# BSPD_4.net
KiCad netlist of a schematic drawn in EAGLE
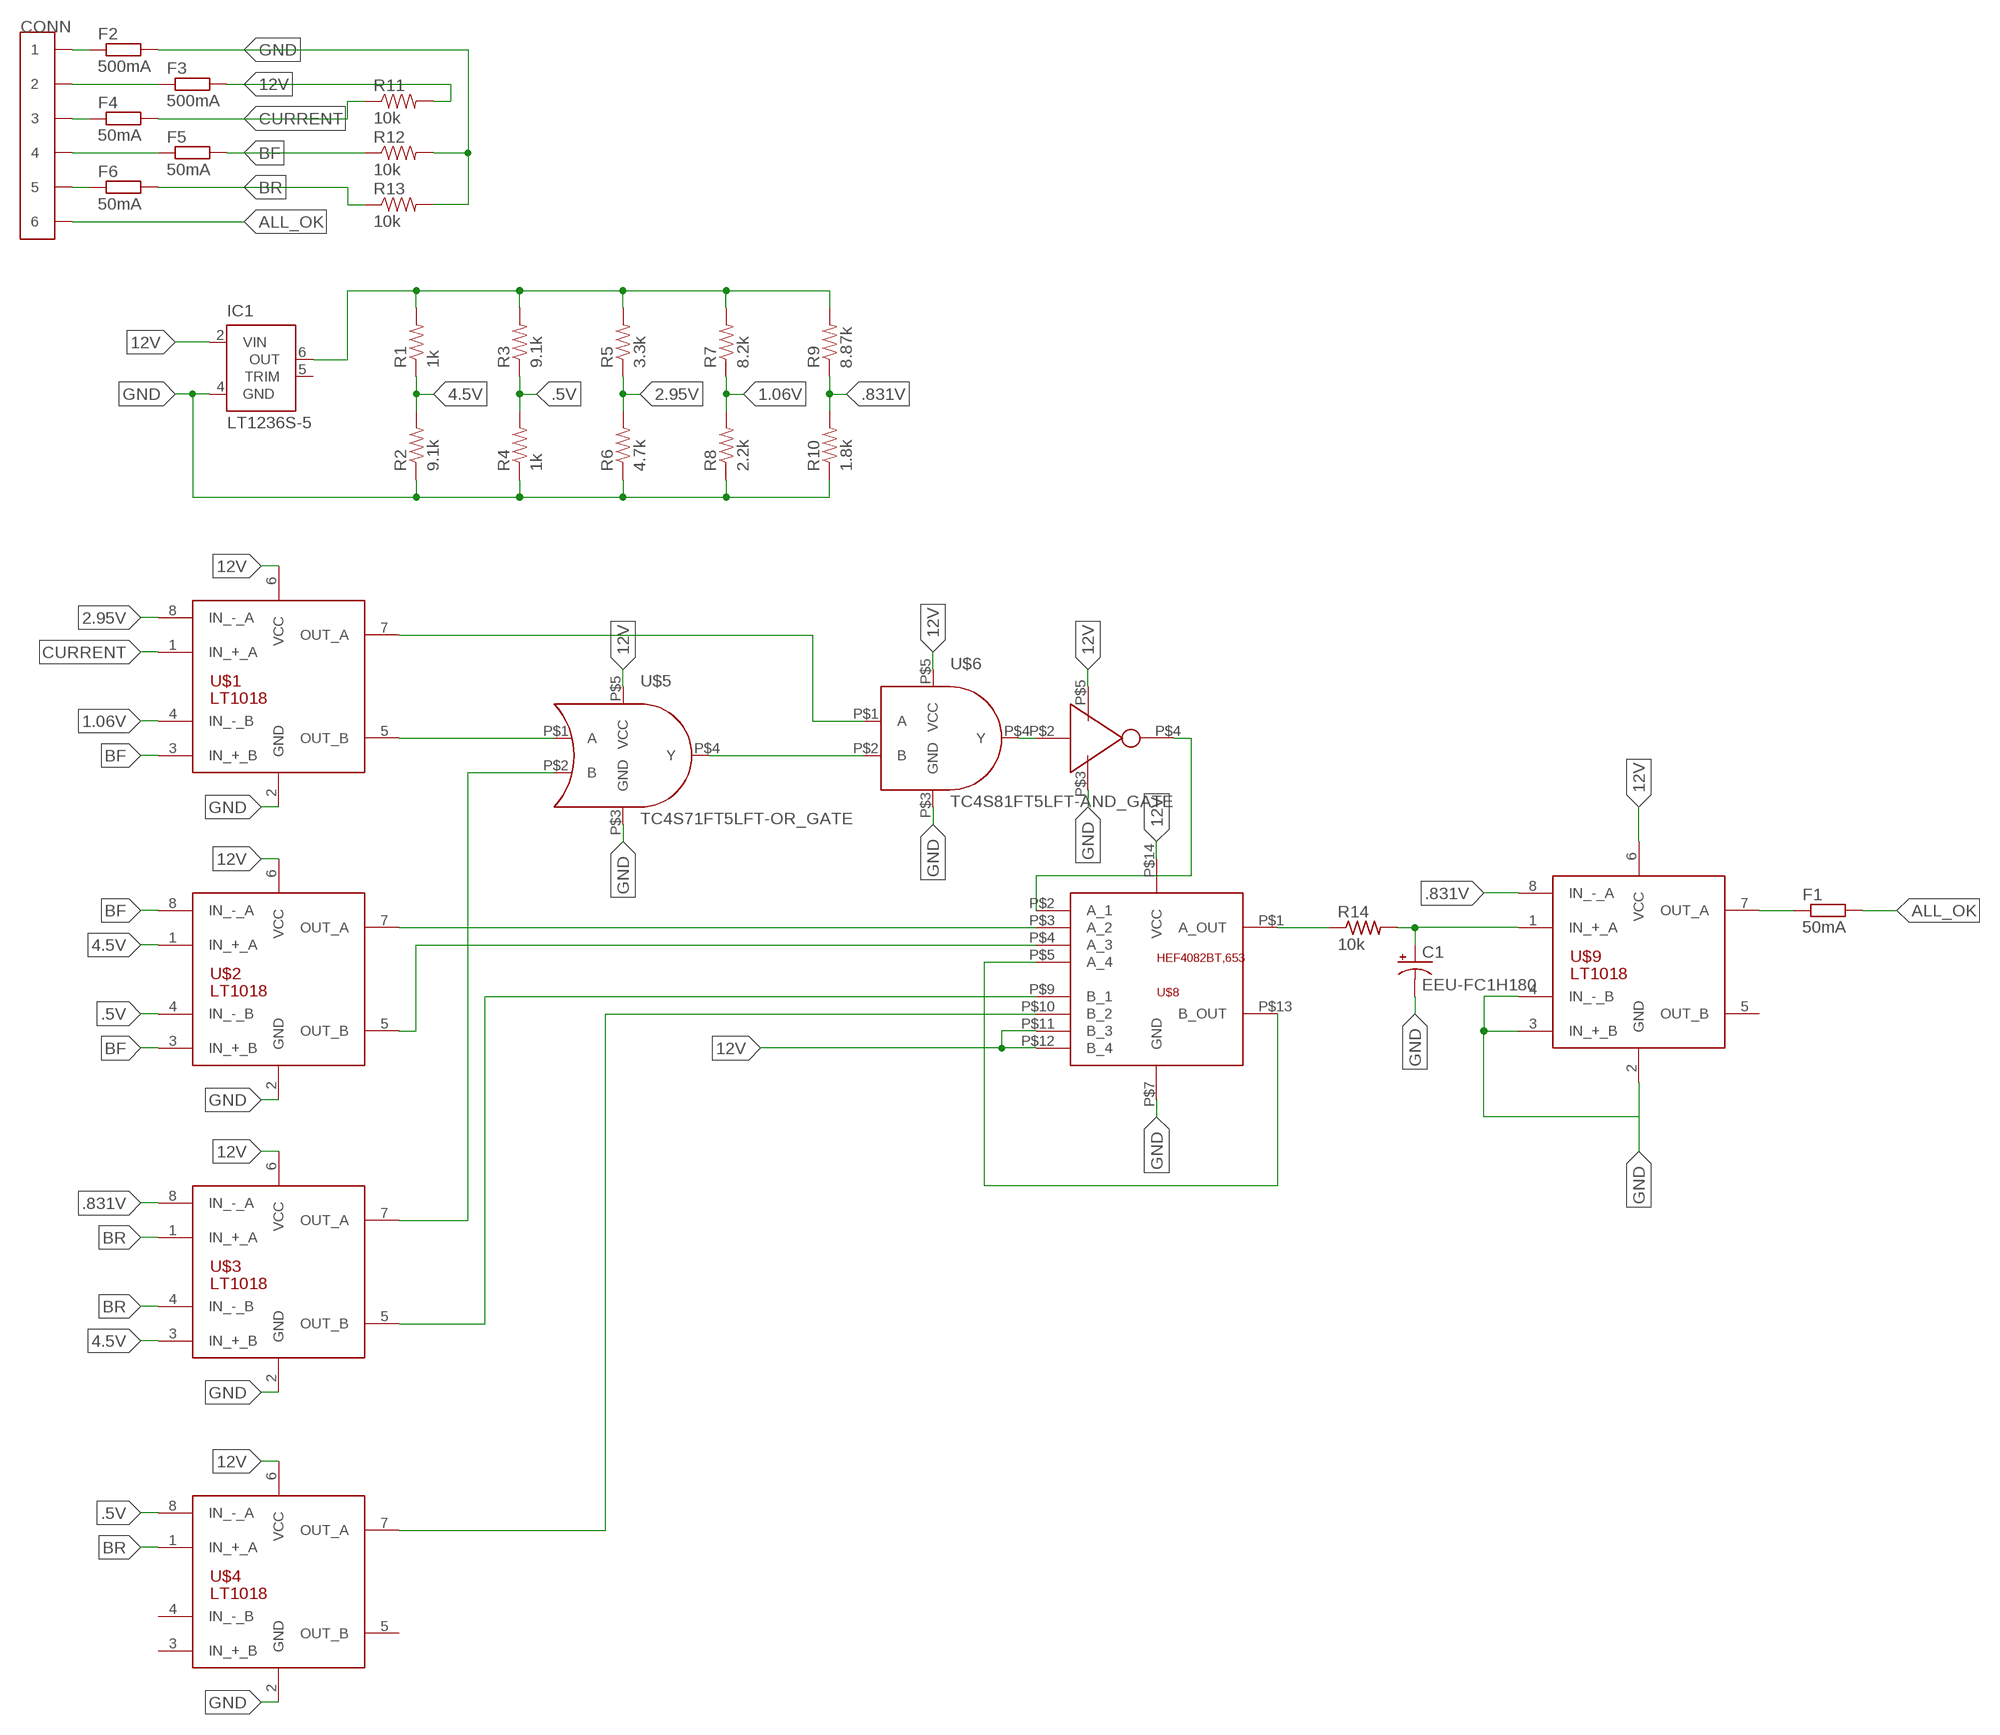
[diagram p0: schematic, sheet 1]

(export (version "E")
  (design (tool "Eeschema 10.0.6"))
  (components
    (comp (ref "C1")
      (value "EEU-FC1H180")
      (footprint "eagle-import:E2-5")
      (libsource (lib "eagle-import") (part "CPOL-USE2-5"))
    )
    (comp (ref "CONN")
      (value "CONN_6")
      (footprint "eagle-import:CONNECTOR_6")
      (libsource (lib "eagle-import") (part "CONN_6"))
    )
    (comp (ref "F1")
      (value "50mA")
      (footprint "eagle-import:R0603")
      (libsource (lib "eagle-import") (part "R-EU_R0603"))
    )
    (comp (ref "F2")
      (value "500mA")
      (footprint "eagle-import:R0603")
      (libsource (lib "eagle-import") (part "R-EU_R0603"))
    )
    (comp (ref "F3")
      (value "500mA")
      (footprint "eagle-import:R0603")
      (libsource (lib "eagle-import") (part "R-EU_R0603"))
    )
    (comp (ref "F4")
      (value "50mA")
      (footprint "eagle-import:R0603")
      (libsource (lib "eagle-import") (part "R-EU_R0603"))
    )
    (comp (ref "F5")
      (value "50mA")
      (footprint "eagle-import:R0603")
      (libsource (lib "eagle-import") (part "R-EU_R0603"))
    )
    (comp (ref "F6")
      (value "50mA")
      (footprint "eagle-import:R0603")
      (libsource (lib "eagle-import") (part "R-EU_R0603"))
    )
    (comp (ref "IC1")
      (value "LT1236S-5")
      (footprint "eagle-import:SOIC8")
      (libsource (lib "eagle-import") (part "LT1236?S-5"))
    )
    (comp (ref "R1")
      (value "1k")
      (footprint "eagle-import:0603-RES")
      (libsource (lib "eagle-import") (part "RESISTOR0603"))
    )
    (comp (ref "R2")
      (value "9.1k")
      (footprint "eagle-import:0603-RES")
      (libsource (lib "eagle-import") (part "RESISTOR0603"))
    )
    (comp (ref "R3")
      (value "9.1k")
      (footprint "eagle-import:0603-RES")
      (libsource (lib "eagle-import") (part "RESISTOR0603"))
    )
    (comp (ref "R4")
      (value "1k")
      (footprint "eagle-import:0603-RES")
      (libsource (lib "eagle-import") (part "RESISTOR0603"))
    )
    (comp (ref "R5")
      (value "3.3k")
      (footprint "eagle-import:0603-RES")
      (libsource (lib "eagle-import") (part "RESISTOR0603"))
    )
    (comp (ref "R6")
      (value "4.7k")
      (footprint "eagle-import:0603-RES")
      (libsource (lib "eagle-import") (part "RESISTOR0603"))
    )
    (comp (ref "R7")
      (value "8.2k")
      (footprint "eagle-import:0603-RES")
      (libsource (lib "eagle-import") (part "RESISTOR0603"))
    )
    (comp (ref "R8")
      (value "2.2k")
      (footprint "eagle-import:0603-RES")
      (libsource (lib "eagle-import") (part "RESISTOR0603"))
    )
    (comp (ref "R9")
      (value "8.87k")
      (footprint "eagle-import:0603-RES")
      (libsource (lib "eagle-import") (part "RESISTOR0603"))
    )
    (comp (ref "R10")
      (value "1.8k")
      (footprint "eagle-import:0603-RES")
      (libsource (lib "eagle-import") (part "RESISTOR0603"))
    )
    (comp (ref "R11")
      (value "10k")
      (footprint "eagle-import:0603-RES")
      (libsource (lib "eagle-import") (part "RESISTOR0603"))
    )
    (comp (ref "R12")
      (value "10k")
      (footprint "eagle-import:0603-RES")
      (libsource (lib "eagle-import") (part "RESISTOR0603"))
    )
    (comp (ref "R13")
      (value "10k")
      (footprint "eagle-import:0603-RES")
      (libsource (lib "eagle-import") (part "RESISTOR0603"))
    )
    (comp (ref "R14")
      (value "10k")
      (footprint "eagle-import:R0603")
      (libsource (lib "eagle-import") (part "R-US_R0603"))
    )
    (comp (ref "U$1")
      (value "LT1018")
      (footprint "eagle-import:SOIC8")
      (libsource (lib "eagle-import") (part "LT1018"))
    )
    (comp (ref "U$2")
      (value "LT1018")
      (footprint "eagle-import:SOIC8")
      (libsource (lib "eagle-import") (part "LT1018"))
    )
    (comp (ref "U$3")
      (value "LT1018")
      (footprint "eagle-import:SOIC8")
      (libsource (lib "eagle-import") (part "LT1018"))
    )
    (comp (ref "U$4")
      (value "LT1018")
      (footprint "eagle-import:SOIC8")
      (libsource (lib "eagle-import") (part "LT1018"))
    )
    (comp (ref "U$5")
      (value "TC4S71FT5LFT-OR_GATE")
      (footprint "eagle-import:SSOP5-P-0.95")
      (libsource (lib "eagle-import") (part "TC4S71FT5LFT-OR_GATE"))
    )
    (comp (ref "U$6")
      (value "TC4S81FT5LFT-AND_GATE")
      (footprint "eagle-import:SSOP5-P-0.95")
      (libsource (lib "eagle-import") (part "TC4S81FT5LFT-AND_GATE"))
    )
    (comp (ref "U$7")
      (value "TC4S69F(TE85L,F)")
      (footprint "eagle-import:SSOP5-P-0.95")
      (libsource (lib "eagle-import") (part "TC4S69F(TE85L,F)"))
    )
    (comp (ref "U$8")
      (value "HEF4082BT,653")
      (footprint "eagle-import:NXP_14_SOIC")
      (libsource (lib "eagle-import") (part "HEF4082BT,653"))
    )
    (comp (ref "U$9")
      (value "LT1018")
      (footprint "eagle-import:SOIC8")
      (libsource (lib "eagle-import") (part "LT1018"))
    )
  )
  (nets
    (net (code "1") (name ".5V") (class "Default")
      (node (ref "R3") (pin "1") (pinfunction "1_1") (pintype "passive"))
      (node (ref "R4") (pin "2") (pinfunction "2_2") (pintype "passive"))
      (node (ref "U$2") (pin "4") (pinfunction "IN_-_B_4") (pintype "input"))
      (node (ref "U$4") (pin "8") (pinfunction "IN_-_A_8") (pintype "input"))
    )
    (net (code "2") (name ".831V") (class "Default")
      (node (ref "R10") (pin "2") (pinfunction "2_2") (pintype "passive"))
      (node (ref "R9") (pin "1") (pinfunction "1_1") (pintype "passive"))
      (node (ref "U$3") (pin "8") (pinfunction "IN_-_A_8") (pintype "input"))
      (node (ref "U$9") (pin "8") (pinfunction "IN_-_A_8") (pintype "input"))
    )
    (net (code "3") (name "1.06V") (class "Default")
      (node (ref "R7") (pin "1") (pinfunction "1_1") (pintype "passive"))
      (node (ref "R8") (pin "2") (pinfunction "2_2") (pintype "passive"))
      (node (ref "U$1") (pin "4") (pinfunction "IN_-_B_4") (pintype "input"))
    )
    (net (code "4") (name "2.95V") (class "Default")
      (node (ref "R5") (pin "1") (pinfunction "1_1") (pintype "passive"))
      (node (ref "R6") (pin "2") (pinfunction "2_2") (pintype "passive"))
      (node (ref "U$1") (pin "8") (pinfunction "IN_-_A_8") (pintype "input"))
    )
    (net (code "5") (name "4.5V") (class "Default")
      (node (ref "R1") (pin "1") (pinfunction "1_1") (pintype "passive"))
      (node (ref "R2") (pin "2") (pinfunction "2_2") (pintype "passive"))
      (node (ref "U$2") (pin "1") (pinfunction "IN_+_A_1") (pintype "input"))
      (node (ref "U$3") (pin "3") (pinfunction "IN_+_B_3") (pintype "input"))
    )
    (net (code "6") (name "12V") (class "Default")
      (node (ref "F3") (pin "2") (pinfunction "2_2") (pintype "passive"))
      (node (ref "IC1") (pin "2") (pinfunction "VIN_2") (pintype "input"))
      (node (ref "R11") (pin "2") (pinfunction "2_2") (pintype "passive"))
      (node (ref "U$1") (pin "6") (pinfunction "VCC_6") (pintype "power_in"))
      (node (ref "U$2") (pin "6") (pinfunction "VCC_6") (pintype "power_in"))
      (node (ref "U$3") (pin "6") (pinfunction "VCC_6") (pintype "power_in"))
      (node (ref "U$4") (pin "6") (pinfunction "VCC_6") (pintype "power_in"))
      (node (ref "U$5") (pin "P$5") (pinfunction "VCC_P$5") (pintype "bidirectional"))
      (node (ref "U$6") (pin "P$5") (pinfunction "VCC_P$5") (pintype "bidirectional"))
      (node (ref "U$7") (pin "P$5") (pinfunction "VCC_P$5") (pintype "power_in"))
      (node (ref "U$8") (pin "P$11") (pinfunction "B_3_P$11") (pintype "open_collector"))
      (node (ref "U$8") (pin "P$12") (pinfunction "B_4_P$12") (pintype "open_collector"))
      (node (ref "U$8") (pin "P$14") (pinfunction "VCC_P$14") (pintype "power_in"))
      (node (ref "U$9") (pin "6") (pinfunction "VCC_6") (pintype "power_in"))
    )
    (net (code "7") (name "ALL_OK") (class "Default")
      (node (ref "CONN") (pin "11") (pinfunction "6_11") (pintype "bidirectional"))
      (node (ref "CONN") (pin "12") (pinfunction "6_12") (pintype "bidirectional"))
      (node (ref "F1") (pin "2") (pinfunction "2_2") (pintype "passive"))
    )
    (net (code "8") (name "BF") (class "Default")
      (node (ref "F5") (pin "2") (pinfunction "2_2") (pintype "passive"))
      (node (ref "R12") (pin "1") (pinfunction "1_1") (pintype "passive"))
      (node (ref "U$1") (pin "3") (pinfunction "IN_+_B_3") (pintype "input"))
      (node (ref "U$2") (pin "3") (pinfunction "IN_+_B_3") (pintype "input"))
      (node (ref "U$2") (pin "8") (pinfunction "IN_-_A_8") (pintype "input"))
    )
    (net (code "9") (name "BR") (class "Default")
      (node (ref "F6") (pin "2") (pinfunction "2_2") (pintype "passive"))
      (node (ref "R13") (pin "1") (pinfunction "1_1") (pintype "passive"))
      (node (ref "U$3") (pin "1") (pinfunction "IN_+_A_1") (pintype "input"))
      (node (ref "U$3") (pin "4") (pinfunction "IN_-_B_4") (pintype "input"))
      (node (ref "U$4") (pin "1") (pinfunction "IN_+_A_1") (pintype "input"))
    )
    (net (code "10") (name "CURRENT") (class "Default")
      (node (ref "F4") (pin "2") (pinfunction "2_2") (pintype "passive"))
      (node (ref "R11") (pin "1") (pinfunction "1_1") (pintype "passive"))
      (node (ref "U$1") (pin "1") (pinfunction "IN_+_A_1") (pintype "input"))
    )
    (net (code "11") (name "GND") (class "Default")
      (node (ref "C1") (pin "-") (pinfunction "-_-") (pintype "passive"))
      (node (ref "F2") (pin "2") (pinfunction "2_2") (pintype "passive"))
      (node (ref "IC1") (pin "4") (pinfunction "GND_4") (pintype "power_in"))
      (node (ref "R10") (pin "1") (pinfunction "1_1") (pintype "passive"))
      (node (ref "R12") (pin "2") (pinfunction "2_2") (pintype "passive"))
      (node (ref "R13") (pin "2") (pinfunction "2_2") (pintype "passive"))
      (node (ref "R2") (pin "1") (pinfunction "1_1") (pintype "passive"))
      (node (ref "R4") (pin "1") (pinfunction "1_1") (pintype "passive"))
      (node (ref "R6") (pin "1") (pinfunction "1_1") (pintype "passive"))
      (node (ref "R8") (pin "1") (pinfunction "1_1") (pintype "passive"))
      (node (ref "U$1") (pin "2") (pinfunction "GND_2") (pintype "power_in"))
      (node (ref "U$2") (pin "2") (pinfunction "GND_2") (pintype "power_in"))
      (node (ref "U$3") (pin "2") (pinfunction "GND_2") (pintype "power_in"))
      (node (ref "U$4") (pin "2") (pinfunction "GND_2") (pintype "power_in"))
      (node (ref "U$5") (pin "P$3") (pinfunction "GND_P$3") (pintype "bidirectional"))
      (node (ref "U$6") (pin "P$3") (pinfunction "GND_P$3") (pintype "bidirectional"))
      (node (ref "U$7") (pin "P$3") (pinfunction "GND_P$3") (pintype "power_in"))
      (node (ref "U$8") (pin "P$7") (pinfunction "GND_P$7") (pintype "power_in"))
      (node (ref "U$9") (pin "2") (pinfunction "GND_2") (pintype "power_in"))
      (node (ref "U$9") (pin "3") (pinfunction "IN_+_B_3") (pintype "input"))
      (node (ref "U$9") (pin "4") (pinfunction "IN_-_B_4") (pintype "input"))
    )
    (net (code "12") (name "Net-(CONN-1-Pad2)") (class "Default")
      (node (ref "CONN") (pin "1") (pinfunction "1_1") (pintype "bidirectional"))
      (node (ref "CONN") (pin "2") (pinfunction "1_2") (pintype "bidirectional"))
      (node (ref "F2") (pin "1") (pinfunction "1_1") (pintype "passive"))
    )
    (net (code "13") (name "Net-(CONN-2-Pad3)") (class "Default")
      (node (ref "CONN") (pin "3") (pinfunction "2_3") (pintype "bidirectional"))
      (node (ref "CONN") (pin "4") (pinfunction "2_4") (pintype "bidirectional"))
      (node (ref "F3") (pin "1") (pinfunction "1_1") (pintype "passive"))
    )
    (net (code "14") (name "Net-(CONN-3-Pad5)") (class "Default")
      (node (ref "CONN") (pin "5") (pinfunction "3_5") (pintype "bidirectional"))
      (node (ref "CONN") (pin "6") (pinfunction "3_6") (pintype "bidirectional"))
      (node (ref "F4") (pin "1") (pinfunction "1_1") (pintype "passive"))
    )
    (net (code "15") (name "Net-(CONN-4-Pad7)") (class "Default")
      (node (ref "CONN") (pin "7") (pinfunction "4_7") (pintype "bidirectional"))
      (node (ref "CONN") (pin "8") (pinfunction "4_8") (pintype "bidirectional"))
      (node (ref "F5") (pin "1") (pinfunction "1_1") (pintype "passive"))
    )
    (net (code "16") (name "Net-(CONN-5-Pad10)") (class "Default")
      (node (ref "CONN") (pin "10") (pinfunction "5_10") (pintype "bidirectional"))
      (node (ref "CONN") (pin "9") (pinfunction "5_9") (pintype "bidirectional"))
      (node (ref "F6") (pin "1") (pinfunction "1_1") (pintype "passive"))
    )
    (net (code "17") (name "Net-(IC1-OUT)") (class "Default")
      (node (ref "IC1") (pin "6") (pinfunction "OUT_6") (pintype "input"))
      (node (ref "R1") (pin "2") (pinfunction "2_2") (pintype "passive"))
      (node (ref "R3") (pin "2") (pinfunction "2_2") (pintype "passive"))
      (node (ref "R5") (pin "2") (pinfunction "2_2") (pintype "passive"))
      (node (ref "R7") (pin "2") (pinfunction "2_2") (pintype "passive"))
      (node (ref "R9") (pin "2") (pinfunction "2_2") (pintype "passive"))
    )
    (net (code "18") (name "Net-(U$1-OUT_A)") (class "Default")
      (node (ref "U$1") (pin "7") (pinfunction "OUT_A_7") (pintype "output"))
      (node (ref "U$6") (pin "P$1") (pinfunction "A_P$1") (pintype "bidirectional"))
    )
    (net (code "19") (name "Net-(U$1-OUT_B)") (class "Default")
      (node (ref "U$1") (pin "5") (pinfunction "OUT_B_5") (pintype "output"))
      (node (ref "U$5") (pin "P$1") (pinfunction "A_P$1") (pintype "bidirectional"))
    )
    (net (code "20") (name "Net-(U$2-OUT_A)") (class "Default")
      (node (ref "U$2") (pin "7") (pinfunction "OUT_A_7") (pintype "output"))
      (node (ref "U$8") (pin "P$3") (pinfunction "A_2_P$3") (pintype "open_collector"))
    )
    (net (code "21") (name "Net-(U$2-OUT_B)") (class "Default")
      (node (ref "U$2") (pin "5") (pinfunction "OUT_B_5") (pintype "output"))
      (node (ref "U$8") (pin "P$4") (pinfunction "A_3_P$4") (pintype "open_collector"))
    )
    (net (code "22") (name "Net-(U$3-OUT_A)") (class "Default")
      (node (ref "U$3") (pin "7") (pinfunction "OUT_A_7") (pintype "output"))
      (node (ref "U$5") (pin "P$2") (pinfunction "B_P$2") (pintype "bidirectional"))
    )
    (net (code "23") (name "Net-(U$3-OUT_B)") (class "Default")
      (node (ref "U$3") (pin "5") (pinfunction "OUT_B_5") (pintype "output"))
      (node (ref "U$8") (pin "P$9") (pinfunction "B_1_P$9") (pintype "open_collector"))
    )
    (net (code "24") (name "Net-(U$4-OUT_A)") (class "Default")
      (node (ref "U$4") (pin "7") (pinfunction "OUT_A_7") (pintype "output"))
      (node (ref "U$8") (pin "P$10") (pinfunction "B_2_P$10") (pintype "open_collector"))
    )
    (net (code "25") (name "Net-(U$5-Y)") (class "Default")
      (node (ref "U$5") (pin "P$4") (pinfunction "Y_P$4") (pintype "bidirectional"))
      (node (ref "U$6") (pin "P$2") (pinfunction "B_P$2") (pintype "bidirectional"))
    )
    (net (code "26") (name "Net-(U$6-Y)") (class "Default")
      (node (ref "U$6") (pin "P$4") (pinfunction "Y_P$4") (pintype "bidirectional"))
      (node (ref "U$7") (pin "P$2") (pinfunction "IN_P$2") (pintype "input"))
    )
    (net (code "27") (name "Net-(U$7-OUT)") (class "Default")
      (node (ref "U$7") (pin "P$4") (pinfunction "OUT_P$4") (pintype "output"))
      (node (ref "U$8") (pin "P$2") (pinfunction "A_1_P$2") (pintype "open_collector"))
    )
    (net (code "28") (name "Net-(U$8-A_4)") (class "Default")
      (node (ref "U$8") (pin "P$13") (pinfunction "B_OUT_P$13") (pintype "output"))
      (node (ref "U$8") (pin "P$5") (pinfunction "A_4_P$5") (pintype "open_collector"))
    )
    (net (code "29") (name "Net-(U$8-A_OUT)") (class "Default")
      (node (ref "R14") (pin "1") (pinfunction "1_1") (pintype "passive"))
      (node (ref "U$8") (pin "P$1") (pinfunction "A_OUT_P$1") (pintype "output"))
    )
    (net (code "30") (name "Net-(U$9-IN_+_A)") (class "Default")
      (node (ref "C1") (pin "+") (pinfunction "+_+") (pintype "passive"))
      (node (ref "R14") (pin "2") (pinfunction "2_2") (pintype "passive"))
      (node (ref "U$9") (pin "1") (pinfunction "IN_+_A_1") (pintype "input"))
    )
    (net (code "31") (name "Net-(U$9-OUT_A)") (class "Default")
      (node (ref "F1") (pin "1") (pinfunction "1_1") (pintype "passive"))
      (node (ref "U$9") (pin "7") (pinfunction "OUT_A_7") (pintype "output"))
    )
    (net (code "32") (name "unconnected-(IC1-TRIM-Pad5)") (class "Default")
      (node (ref "IC1") (pin "5") (pinfunction "TRIM_5") (pintype "passive"))
    )
    (net (code "33") (name "unconnected-(U$4-IN_+_B-Pad3)") (class "Default")
      (node (ref "U$4") (pin "3") (pinfunction "IN_+_B_3") (pintype "input"))
    )
    (net (code "34") (name "unconnected-(U$4-IN_-_B-Pad4)") (class "Default")
      (node (ref "U$4") (pin "4") (pinfunction "IN_-_B_4") (pintype "input"))
    )
    (net (code "35") (name "unconnected-(U$4-OUT_B-Pad5)") (class "Default")
      (node (ref "U$4") (pin "5") (pinfunction "OUT_B_5") (pintype "output"))
    )
    (net (code "36") (name "unconnected-(U$9-OUT_B-Pad5)") (class "Default")
      (node (ref "U$9") (pin "5") (pinfunction "OUT_B_5") (pintype "output"))
    )
  )
)
